# Callisto_Header_Test_Board.net
KiCad netlist of a schematic drawn in EAGLE
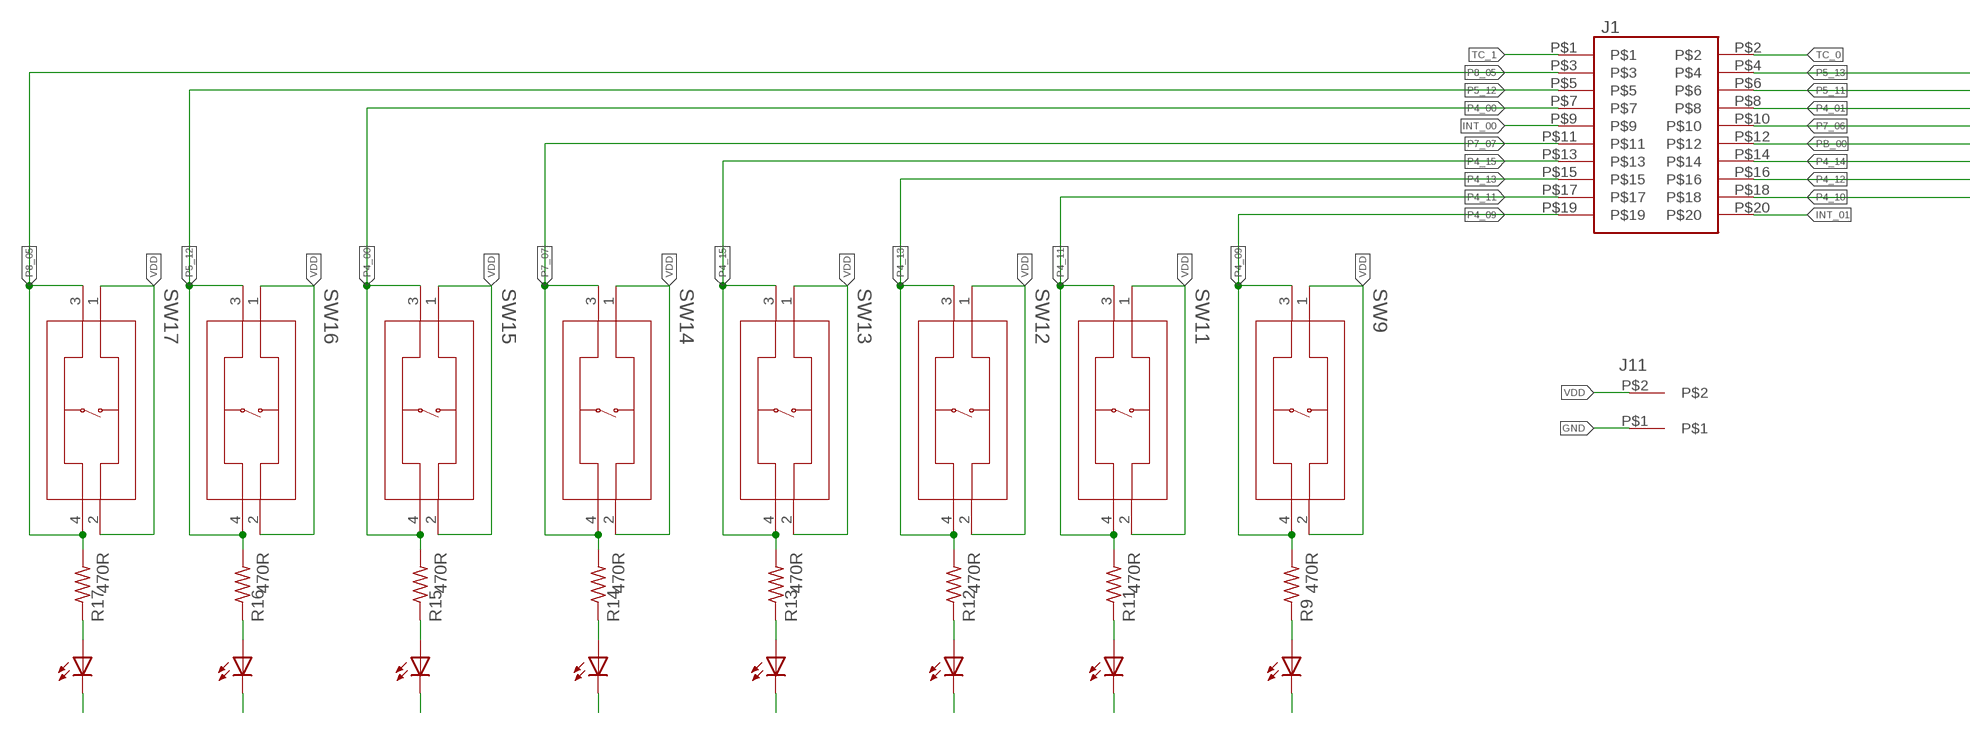
[diagram p0: schematic, sheet 1, part 1 of 2]
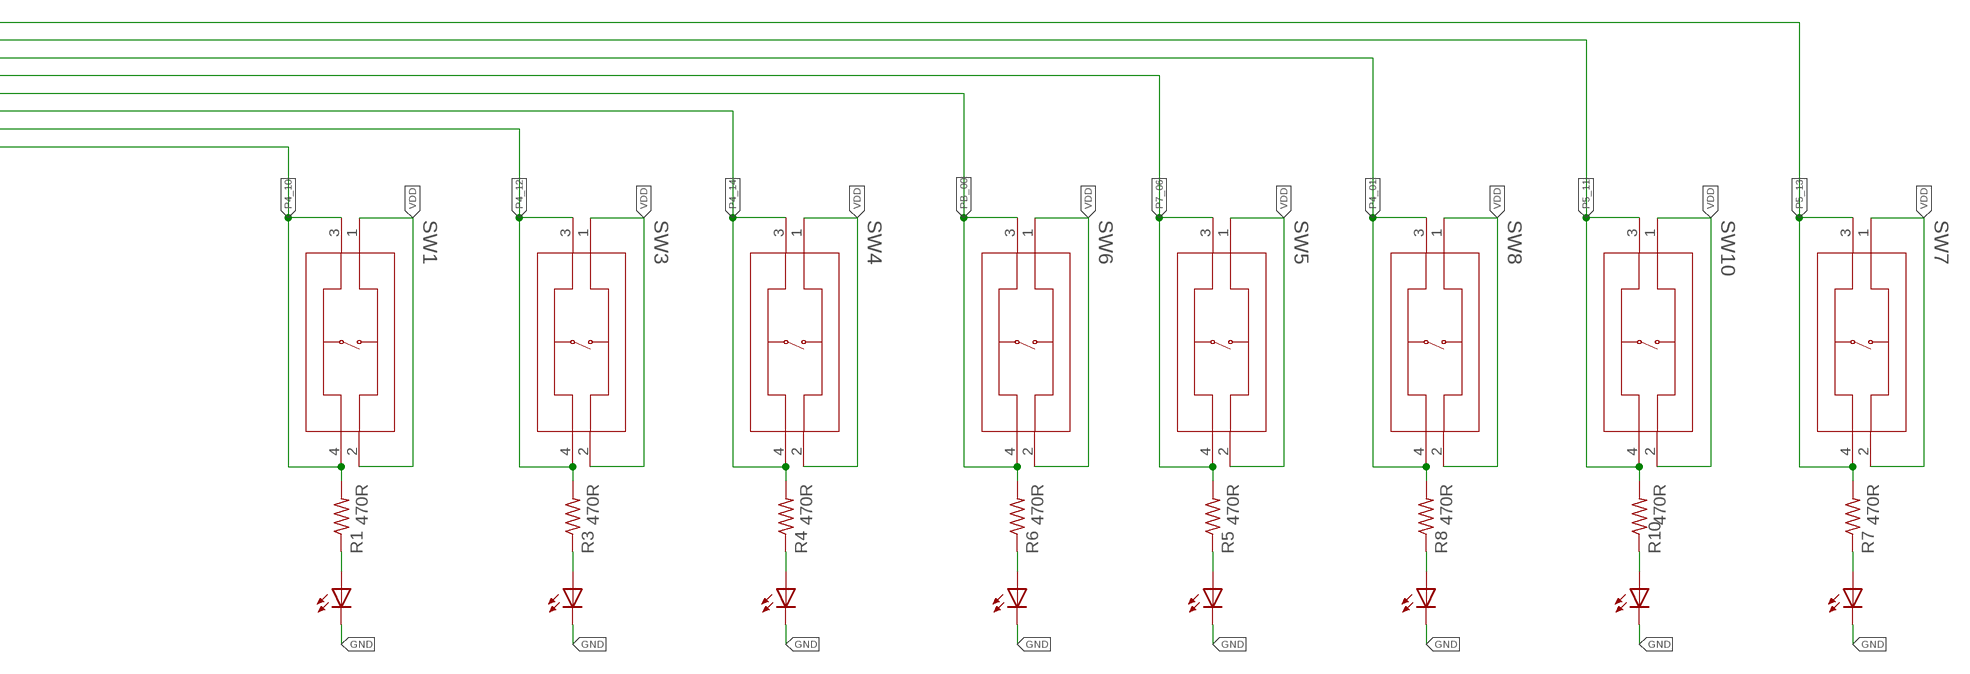
[diagram p1: schematic, sheet 1, part 2 of 2]

(export (version "E")
  (design (tool "Eeschema 10.0.6"))
  (components
    (comp (ref "J1")
      (value "20-pos")
      (footprint "eagle-import:2_X_10_.1_INCH")
      (fields (field (name "PARTNO") "67996-420HLF"))
      (libsource (lib "eagle-import") (part "2_X_10_HEADER_GENERIC"))
    )
    (comp (ref "J11")
      (value "2-pos")
      (footprint "eagle-import:2_3.81MM_PITCH")
      (fields (field (name "PARTNO") "691322310002"))
      (libsource (lib "eagle-import") (part "3.81MM_1_X_2_RT_ANGLE_PLUG_HEADER"))
    )
    (comp (ref "LED1")
      (value "Green")
      (footprint "eagle-import:0805")
      (fields (field (name "PARTNO") "LG R971-KN-1"))
      (libsource (lib "eagle-import") (part "LED_0805_GREEN"))
    )
    (comp (ref "LED3")
      (value "Green")
      (footprint "eagle-import:0805")
      (fields (field (name "PARTNO") "LG R971-KN-1"))
      (libsource (lib "eagle-import") (part "LED_0805_GREEN"))
    )
    (comp (ref "LED4")
      (value "Green")
      (footprint "eagle-import:0805")
      (fields (field (name "PARTNO") "LG R971-KN-1"))
      (libsource (lib "eagle-import") (part "LED_0805_GREEN"))
    )
    (comp (ref "LED5")
      (value "Green")
      (footprint "eagle-import:0805")
      (fields (field (name "PARTNO") "LG R971-KN-1"))
      (libsource (lib "eagle-import") (part "LED_0805_GREEN"))
    )
    (comp (ref "LED6")
      (value "Green")
      (footprint "eagle-import:0805")
      (fields (field (name "PARTNO") "LG R971-KN-1"))
      (libsource (lib "eagle-import") (part "LED_0805_GREEN"))
    )
    (comp (ref "LED7")
      (value "Green")
      (footprint "eagle-import:0805")
      (fields (field (name "PARTNO") "LG R971-KN-1"))
      (libsource (lib "eagle-import") (part "LED_0805_GREEN"))
    )
    (comp (ref "LED8")
      (value "Green")
      (footprint "eagle-import:0805")
      (fields (field (name "PARTNO") "LG R971-KN-1"))
      (libsource (lib "eagle-import") (part "LED_0805_GREEN"))
    )
    (comp (ref "LED9")
      (value "Green")
      (footprint "eagle-import:0805")
      (fields (field (name "PARTNO") "LG R971-KN-1"))
      (libsource (lib "eagle-import") (part "LED_0805_GREEN"))
    )
    (comp (ref "LED10")
      (value "Green")
      (footprint "eagle-import:0805")
      (fields (field (name "PARTNO") "LG R971-KN-1"))
      (libsource (lib "eagle-import") (part "LED_0805_GREEN"))
    )
    (comp (ref "LED11")
      (value "Green")
      (footprint "eagle-import:0805")
      (fields (field (name "PARTNO") "LG R971-KN-1"))
      (libsource (lib "eagle-import") (part "LED_0805_GREEN"))
    )
    (comp (ref "LED12")
      (value "Green")
      (footprint "eagle-import:0805")
      (fields (field (name "PARTNO") "LG R971-KN-1"))
      (libsource (lib "eagle-import") (part "LED_0805_GREEN"))
    )
    (comp (ref "LED13")
      (value "Green")
      (footprint "eagle-import:0805")
      (fields (field (name "PARTNO") "LG R971-KN-1"))
      (libsource (lib "eagle-import") (part "LED_0805_GREEN"))
    )
    (comp (ref "LED14")
      (value "Green")
      (footprint "eagle-import:0805")
      (fields (field (name "PARTNO") "LG R971-KN-1"))
      (libsource (lib "eagle-import") (part "LED_0805_GREEN"))
    )
    (comp (ref "LED15")
      (value "Green")
      (footprint "eagle-import:0805")
      (fields (field (name "PARTNO") "LG R971-KN-1"))
      (libsource (lib "eagle-import") (part "LED_0805_GREEN"))
    )
    (comp (ref "LED16")
      (value "Green")
      (footprint "eagle-import:0805")
      (fields (field (name "PARTNO") "LG R971-KN-1"))
      (libsource (lib "eagle-import") (part "LED_0805_GREEN"))
    )
    (comp (ref "LED17")
      (value "Green")
      (footprint "eagle-import:0805")
      (fields (field (name "PARTNO") "LG R971-KN-1"))
      (libsource (lib "eagle-import") (part "LED_0805_GREEN"))
    )
    (comp (ref "R1")
      (value "470R")
      (footprint "eagle-import:0402")
      (libsource (lib "eagle-import") (part "R_0402"))
    )
    (comp (ref "R3")
      (value "470R")
      (footprint "eagle-import:0402")
      (libsource (lib "eagle-import") (part "R_0402"))
    )
    (comp (ref "R4")
      (value "470R")
      (footprint "eagle-import:0402")
      (libsource (lib "eagle-import") (part "R_0402"))
    )
    (comp (ref "R5")
      (value "470R")
      (footprint "eagle-import:0402")
      (libsource (lib "eagle-import") (part "R_0402"))
    )
    (comp (ref "R6")
      (value "470R")
      (footprint "eagle-import:0402")
      (libsource (lib "eagle-import") (part "R_0402"))
    )
    (comp (ref "R7")
      (value "470R")
      (footprint "eagle-import:0402")
      (libsource (lib "eagle-import") (part "R_0402"))
    )
    (comp (ref "R8")
      (value "470R")
      (footprint "eagle-import:0402")
      (libsource (lib "eagle-import") (part "R_0402"))
    )
    (comp (ref "R9")
      (value "470R")
      (footprint "eagle-import:0402")
      (libsource (lib "eagle-import") (part "R_0402"))
    )
    (comp (ref "R10")
      (value "470R")
      (footprint "eagle-import:0402")
      (libsource (lib "eagle-import") (part "R_0402"))
    )
    (comp (ref "R11")
      (value "470R")
      (footprint "eagle-import:0402")
      (libsource (lib "eagle-import") (part "R_0402"))
    )
    (comp (ref "R12")
      (value "470R")
      (footprint "eagle-import:0402")
      (libsource (lib "eagle-import") (part "R_0402"))
    )
    (comp (ref "R13")
      (value "470R")
      (footprint "eagle-import:0402")
      (libsource (lib "eagle-import") (part "R_0402"))
    )
    (comp (ref "R14")
      (value "470R")
      (footprint "eagle-import:0402")
      (libsource (lib "eagle-import") (part "R_0402"))
    )
    (comp (ref "R15")
      (value "470R")
      (footprint "eagle-import:0402")
      (libsource (lib "eagle-import") (part "R_0402"))
    )
    (comp (ref "R16")
      (value "470R")
      (footprint "eagle-import:0402")
      (libsource (lib "eagle-import") (part "R_0402"))
    )
    (comp (ref "R17")
      (value "470R")
      (footprint "eagle-import:0402")
      (libsource (lib "eagle-import") (part "R_0402"))
    )
    (comp (ref "SW1")
      (value "PTS810SJG250SMTRLFS")
      (footprint "eagle-import:PTS810")
      (fields (field (name "COPYRIGHT") "Copyright (C) 2018 Accelerated Designs. All rights reserved"))
      (libsource (lib "eagle-import") (part "PTS810SJG250SMTRLFS"))
    )
    (comp (ref "SW3")
      (value "PTS810SJG250SMTRLFS")
      (footprint "eagle-import:PTS810")
      (fields (field (name "COPYRIGHT") "Copyright (C) 2018 Accelerated Designs. All rights reserved"))
      (libsource (lib "eagle-import") (part "PTS810SJG250SMTRLFS"))
    )
    (comp (ref "SW4")
      (value "PTS810SJG250SMTRLFS")
      (footprint "eagle-import:PTS810")
      (fields (field (name "COPYRIGHT") "Copyright (C) 2018 Accelerated Designs. All rights reserved"))
      (libsource (lib "eagle-import") (part "PTS810SJG250SMTRLFS"))
    )
    (comp (ref "SW5")
      (value "PTS810SJG250SMTRLFS")
      (footprint "eagle-import:PTS810")
      (fields (field (name "COPYRIGHT") "Copyright (C) 2018 Accelerated Designs. All rights reserved"))
      (libsource (lib "eagle-import") (part "PTS810SJG250SMTRLFS"))
    )
    (comp (ref "SW6")
      (value "PTS810SJG250SMTRLFS")
      (footprint "eagle-import:PTS810")
      (fields (field (name "COPYRIGHT") "Copyright (C) 2018 Accelerated Designs. All rights reserved"))
      (libsource (lib "eagle-import") (part "PTS810SJG250SMTRLFS"))
    )
    (comp (ref "SW7")
      (value "PTS810SJG250SMTRLFS")
      (footprint "eagle-import:PTS810")
      (fields (field (name "COPYRIGHT") "Copyright (C) 2018 Accelerated Designs. All rights reserved"))
      (libsource (lib "eagle-import") (part "PTS810SJG250SMTRLFS"))
    )
    (comp (ref "SW8")
      (value "PTS810SJG250SMTRLFS")
      (footprint "eagle-import:PTS810")
      (fields (field (name "COPYRIGHT") "Copyright (C) 2018 Accelerated Designs. All rights reserved"))
      (libsource (lib "eagle-import") (part "PTS810SJG250SMTRLFS"))
    )
    (comp (ref "SW9")
      (value "PTS810SJG250SMTRLFS")
      (footprint "eagle-import:PTS810")
      (fields (field (name "COPYRIGHT") "Copyright (C) 2018 Accelerated Designs. All rights reserved"))
      (libsource (lib "eagle-import") (part "PTS810SJG250SMTRLFS"))
    )
    (comp (ref "SW10")
      (value "PTS810SJG250SMTRLFS")
      (footprint "eagle-import:PTS810")
      (fields (field (name "COPYRIGHT") "Copyright (C) 2018 Accelerated Designs. All rights reserved"))
      (libsource (lib "eagle-import") (part "PTS810SJG250SMTRLFS"))
    )
    (comp (ref "SW11")
      (value "PTS810SJG250SMTRLFS")
      (footprint "eagle-import:PTS810")
      (fields (field (name "COPYRIGHT") "Copyright (C) 2018 Accelerated Designs. All rights reserved"))
      (libsource (lib "eagle-import") (part "PTS810SJG250SMTRLFS"))
    )
    (comp (ref "SW12")
      (value "PTS810SJG250SMTRLFS")
      (footprint "eagle-import:PTS810")
      (fields (field (name "COPYRIGHT") "Copyright (C) 2018 Accelerated Designs. All rights reserved"))
      (libsource (lib "eagle-import") (part "PTS810SJG250SMTRLFS"))
    )
    (comp (ref "SW13")
      (value "PTS810SJG250SMTRLFS")
      (footprint "eagle-import:PTS810")
      (fields (field (name "COPYRIGHT") "Copyright (C) 2018 Accelerated Designs. All rights reserved"))
      (libsource (lib "eagle-import") (part "PTS810SJG250SMTRLFS"))
    )
    (comp (ref "SW14")
      (value "PTS810SJG250SMTRLFS")
      (footprint "eagle-import:PTS810")
      (fields (field (name "COPYRIGHT") "Copyright (C) 2018 Accelerated Designs. All rights reserved"))
      (libsource (lib "eagle-import") (part "PTS810SJG250SMTRLFS"))
    )
    (comp (ref "SW15")
      (value "PTS810SJG250SMTRLFS")
      (footprint "eagle-import:PTS810")
      (fields (field (name "COPYRIGHT") "Copyright (C) 2018 Accelerated Designs. All rights reserved"))
      (libsource (lib "eagle-import") (part "PTS810SJG250SMTRLFS"))
    )
    (comp (ref "SW16")
      (value "PTS810SJG250SMTRLFS")
      (footprint "eagle-import:PTS810")
      (fields (field (name "COPYRIGHT") "Copyright (C) 2018 Accelerated Designs. All rights reserved"))
      (libsource (lib "eagle-import") (part "PTS810SJG250SMTRLFS"))
    )
    (comp (ref "SW17")
      (value "PTS810SJG250SMTRLFS")
      (footprint "eagle-import:PTS810")
      (fields (field (name "COPYRIGHT") "Copyright (C) 2018 Accelerated Designs. All rights reserved"))
      (libsource (lib "eagle-import") (part "PTS810SJG250SMTRLFS"))
    )
  )
  (nets
    (net (code "1") (name "GND") (class "Default")
      (node (ref "J11") (pin "P$1") (pinfunction "P$1_P$1") (pintype "bidirectional"))
      (node (ref "LED1") (pin "2") (pinfunction "C_2") (pintype "passive"))
      (node (ref "LED10") (pin "2") (pinfunction "C_2") (pintype "passive"))
      (node (ref "LED11") (pin "2") (pinfunction "C_2") (pintype "passive"))
      (node (ref "LED12") (pin "2") (pinfunction "C_2") (pintype "passive"))
      (node (ref "LED13") (pin "2") (pinfunction "C_2") (pintype "passive"))
      (node (ref "LED14") (pin "2") (pinfunction "C_2") (pintype "passive"))
      (node (ref "LED15") (pin "2") (pinfunction "C_2") (pintype "passive"))
      (node (ref "LED16") (pin "2") (pinfunction "C_2") (pintype "passive"))
      (node (ref "LED17") (pin "2") (pinfunction "C_2") (pintype "passive"))
      (node (ref "LED3") (pin "2") (pinfunction "C_2") (pintype "passive"))
      (node (ref "LED4") (pin "2") (pinfunction "C_2") (pintype "passive"))
      (node (ref "LED5") (pin "2") (pinfunction "C_2") (pintype "passive"))
      (node (ref "LED6") (pin "2") (pinfunction "C_2") (pintype "passive"))
      (node (ref "LED7") (pin "2") (pinfunction "C_2") (pintype "passive"))
      (node (ref "LED8") (pin "2") (pinfunction "C_2") (pintype "passive"))
      (node (ref "LED9") (pin "2") (pinfunction "C_2") (pintype "passive"))
    )
    (net (code "2") (name "INT_00") (class "Default")
      (node (ref "J1") (pin "P$9") (pinfunction "P$9_P$9") (pintype "bidirectional"))
    )
    (net (code "3") (name "INT_01") (class "Default")
      (node (ref "J1") (pin "P$20") (pinfunction "P$20_P$20") (pintype "bidirectional"))
    )
    (net (code "4") (name "Net-(LED1-A)") (class "Default")
      (node (ref "LED1") (pin "1") (pinfunction "A_1") (pintype "passive"))
      (node (ref "R1") (pin "P$1") (pinfunction "1_P$1") (pintype "passive"))
    )
    (net (code "5") (name "Net-(LED3-A)") (class "Default")
      (node (ref "LED3") (pin "1") (pinfunction "A_1") (pintype "passive"))
      (node (ref "R3") (pin "P$1") (pinfunction "1_P$1") (pintype "passive"))
    )
    (net (code "6") (name "Net-(LED4-A)") (class "Default")
      (node (ref "LED4") (pin "1") (pinfunction "A_1") (pintype "passive"))
      (node (ref "R4") (pin "P$1") (pinfunction "1_P$1") (pintype "passive"))
    )
    (net (code "7") (name "Net-(LED5-A)") (class "Default")
      (node (ref "LED5") (pin "1") (pinfunction "A_1") (pintype "passive"))
      (node (ref "R5") (pin "P$1") (pinfunction "1_P$1") (pintype "passive"))
    )
    (net (code "8") (name "Net-(LED6-A)") (class "Default")
      (node (ref "LED6") (pin "1") (pinfunction "A_1") (pintype "passive"))
      (node (ref "R6") (pin "P$1") (pinfunction "1_P$1") (pintype "passive"))
    )
    (net (code "9") (name "Net-(LED7-A)") (class "Default")
      (node (ref "LED7") (pin "1") (pinfunction "A_1") (pintype "passive"))
      (node (ref "R7") (pin "P$1") (pinfunction "1_P$1") (pintype "passive"))
    )
    (net (code "10") (name "Net-(LED8-A)") (class "Default")
      (node (ref "LED8") (pin "1") (pinfunction "A_1") (pintype "passive"))
      (node (ref "R8") (pin "P$1") (pinfunction "1_P$1") (pintype "passive"))
    )
    (net (code "11") (name "Net-(LED9-A)") (class "Default")
      (node (ref "LED9") (pin "1") (pinfunction "A_1") (pintype "passive"))
      (node (ref "R9") (pin "P$1") (pinfunction "1_P$1") (pintype "passive"))
    )
    (net (code "12") (name "Net-(LED10-A)") (class "Default")
      (node (ref "LED10") (pin "1") (pinfunction "A_1") (pintype "passive"))
      (node (ref "R10") (pin "P$1") (pinfunction "1_P$1") (pintype "passive"))
    )
    (net (code "13") (name "Net-(LED11-A)") (class "Default")
      (node (ref "LED11") (pin "1") (pinfunction "A_1") (pintype "passive"))
      (node (ref "R11") (pin "P$1") (pinfunction "1_P$1") (pintype "passive"))
    )
    (net (code "14") (name "Net-(LED12-A)") (class "Default")
      (node (ref "LED12") (pin "1") (pinfunction "A_1") (pintype "passive"))
      (node (ref "R12") (pin "P$1") (pinfunction "1_P$1") (pintype "passive"))
    )
    (net (code "15") (name "Net-(LED13-A)") (class "Default")
      (node (ref "LED13") (pin "1") (pinfunction "A_1") (pintype "passive"))
      (node (ref "R13") (pin "P$1") (pinfunction "1_P$1") (pintype "passive"))
    )
    (net (code "16") (name "Net-(LED14-A)") (class "Default")
      (node (ref "LED14") (pin "1") (pinfunction "A_1") (pintype "passive"))
      (node (ref "R14") (pin "P$1") (pinfunction "1_P$1") (pintype "passive"))
    )
    (net (code "17") (name "Net-(LED15-A)") (class "Default")
      (node (ref "LED15") (pin "1") (pinfunction "A_1") (pintype "passive"))
      (node (ref "R15") (pin "P$1") (pinfunction "1_P$1") (pintype "passive"))
    )
    (net (code "18") (name "Net-(LED16-A)") (class "Default")
      (node (ref "LED16") (pin "1") (pinfunction "A_1") (pintype "passive"))
      (node (ref "R16") (pin "P$1") (pinfunction "1_P$1") (pintype "passive"))
    )
    (net (code "19") (name "Net-(LED17-A)") (class "Default")
      (node (ref "LED17") (pin "1") (pinfunction "A_1") (pintype "passive"))
      (node (ref "R17") (pin "P$1") (pinfunction "1_P$1") (pintype "passive"))
    )
    (net (code "20") (name "P4_00") (class "Default")
      (node (ref "J1") (pin "P$7") (pinfunction "P$7_P$7") (pintype "bidirectional"))
      (node (ref "R15") (pin "P$2") (pinfunction "2_P$2") (pintype "passive"))
      (node (ref "SW15") (pin "3") (pinfunction "3_3") (pintype "passive"))
      (node (ref "SW15") (pin "4") (pinfunction "4_4") (pintype "passive"))
    )
    (net (code "21") (name "P4_01") (class "Default")
      (node (ref "J1") (pin "P$8") (pinfunction "P$8_P$8") (pintype "bidirectional"))
      (node (ref "R8") (pin "P$2") (pinfunction "2_P$2") (pintype "passive"))
      (node (ref "SW8") (pin "3") (pinfunction "3_3") (pintype "passive"))
      (node (ref "SW8") (pin "4") (pinfunction "4_4") (pintype "passive"))
    )
    (net (code "22") (name "P4_09") (class "Default")
      (node (ref "J1") (pin "P$19") (pinfunction "P$19_P$19") (pintype "bidirectional"))
      (node (ref "R9") (pin "P$2") (pinfunction "2_P$2") (pintype "passive"))
      (node (ref "SW9") (pin "3") (pinfunction "3_3") (pintype "passive"))
      (node (ref "SW9") (pin "4") (pinfunction "4_4") (pintype "passive"))
    )
    (net (code "23") (name "P4_10") (class "Default")
      (node (ref "J1") (pin "P$18") (pinfunction "P$18_P$18") (pintype "bidirectional"))
      (node (ref "R1") (pin "P$2") (pinfunction "2_P$2") (pintype "passive"))
      (node (ref "SW1") (pin "3") (pinfunction "3_3") (pintype "passive"))
      (node (ref "SW1") (pin "4") (pinfunction "4_4") (pintype "passive"))
    )
    (net (code "24") (name "P4_11") (class "Default")
      (node (ref "J1") (pin "P$17") (pinfunction "P$17_P$17") (pintype "bidirectional"))
      (node (ref "R11") (pin "P$2") (pinfunction "2_P$2") (pintype "passive"))
      (node (ref "SW11") (pin "3") (pinfunction "3_3") (pintype "passive"))
      (node (ref "SW11") (pin "4") (pinfunction "4_4") (pintype "passive"))
    )
    (net (code "25") (name "P4_12") (class "Default")
      (node (ref "J1") (pin "P$16") (pinfunction "P$16_P$16") (pintype "bidirectional"))
      (node (ref "R3") (pin "P$2") (pinfunction "2_P$2") (pintype "passive"))
      (node (ref "SW3") (pin "3") (pinfunction "3_3") (pintype "passive"))
      (node (ref "SW3") (pin "4") (pinfunction "4_4") (pintype "passive"))
    )
    (net (code "26") (name "P4_13") (class "Default")
      (node (ref "J1") (pin "P$15") (pinfunction "P$15_P$15") (pintype "bidirectional"))
      (node (ref "R12") (pin "P$2") (pinfunction "2_P$2") (pintype "passive"))
      (node (ref "SW12") (pin "3") (pinfunction "3_3") (pintype "passive"))
      (node (ref "SW12") (pin "4") (pinfunction "4_4") (pintype "passive"))
    )
    (net (code "27") (name "P4_14") (class "Default")
      (node (ref "J1") (pin "P$14") (pinfunction "P$14_P$14") (pintype "bidirectional"))
      (node (ref "R4") (pin "P$2") (pinfunction "2_P$2") (pintype "passive"))
      (node (ref "SW4") (pin "3") (pinfunction "3_3") (pintype "passive"))
      (node (ref "SW4") (pin "4") (pinfunction "4_4") (pintype "passive"))
    )
    (net (code "28") (name "P4_15") (class "Default")
      (node (ref "J1") (pin "P$13") (pinfunction "P$13_P$13") (pintype "bidirectional"))
      (node (ref "R13") (pin "P$2") (pinfunction "2_P$2") (pintype "passive"))
      (node (ref "SW13") (pin "3") (pinfunction "3_3") (pintype "passive"))
      (node (ref "SW13") (pin "4") (pinfunction "4_4") (pintype "passive"))
    )
    (net (code "29") (name "P5_11") (class "Default")
      (node (ref "J1") (pin "P$6") (pinfunction "P$6_P$6") (pintype "bidirectional"))
      (node (ref "R10") (pin "P$2") (pinfunction "2_P$2") (pintype "passive"))
      (node (ref "SW10") (pin "3") (pinfunction "3_3") (pintype "passive"))
      (node (ref "SW10") (pin "4") (pinfunction "4_4") (pintype "passive"))
    )
    (net (code "30") (name "P5_12") (class "Default")
      (node (ref "J1") (pin "P$5") (pinfunction "P$5_P$5") (pintype "bidirectional"))
      (node (ref "R16") (pin "P$2") (pinfunction "2_P$2") (pintype "passive"))
      (node (ref "SW16") (pin "3") (pinfunction "3_3") (pintype "passive"))
      (node (ref "SW16") (pin "4") (pinfunction "4_4") (pintype "passive"))
    )
    (net (code "31") (name "P5_13") (class "Default")
      (node (ref "J1") (pin "P$4") (pinfunction "P$4_P$4") (pintype "bidirectional"))
      (node (ref "R7") (pin "P$2") (pinfunction "2_P$2") (pintype "passive"))
      (node (ref "SW7") (pin "3") (pinfunction "3_3") (pintype "passive"))
      (node (ref "SW7") (pin "4") (pinfunction "4_4") (pintype "passive"))
    )
    (net (code "32") (name "P7_06") (class "Default")
      (node (ref "J1") (pin "P$10") (pinfunction "P$10_P$10") (pintype "bidirectional"))
      (node (ref "R5") (pin "P$2") (pinfunction "2_P$2") (pintype "passive"))
      (node (ref "SW5") (pin "3") (pinfunction "3_3") (pintype "passive"))
      (node (ref "SW5") (pin "4") (pinfunction "4_4") (pintype "passive"))
    )
    (net (code "33") (name "P7_07") (class "Default")
      (node (ref "J1") (pin "P$11") (pinfunction "P$11_P$11") (pintype "bidirectional"))
      (node (ref "R14") (pin "P$2") (pinfunction "2_P$2") (pintype "passive"))
      (node (ref "SW14") (pin "3") (pinfunction "3_3") (pintype "passive"))
      (node (ref "SW14") (pin "4") (pinfunction "4_4") (pintype "passive"))
    )
    (net (code "34") (name "P8_05") (class "Default")
      (node (ref "J1") (pin "P$3") (pinfunction "P$3_P$3") (pintype "bidirectional"))
      (node (ref "R17") (pin "P$2") (pinfunction "2_P$2") (pintype "passive"))
      (node (ref "SW17") (pin "3") (pinfunction "3_3") (pintype "passive"))
      (node (ref "SW17") (pin "4") (pinfunction "4_4") (pintype "passive"))
    )
    (net (code "35") (name "PB_00") (class "Default")
      (node (ref "J1") (pin "P$12") (pinfunction "P$12_P$12") (pintype "bidirectional"))
      (node (ref "R6") (pin "P$2") (pinfunction "2_P$2") (pintype "passive"))
      (node (ref "SW6") (pin "3") (pinfunction "3_3") (pintype "passive"))
      (node (ref "SW6") (pin "4") (pinfunction "4_4") (pintype "passive"))
    )
    (net (code "36") (name "TC_0") (class "Default")
      (node (ref "J1") (pin "P$2") (pinfunction "P$2_P$2") (pintype "bidirectional"))
    )
    (net (code "37") (name "TC_1") (class "Default")
      (node (ref "J1") (pin "P$1") (pinfunction "P$1_P$1") (pintype "bidirectional"))
    )
    (net (code "38") (name "VDD") (class "Default")
      (node (ref "J11") (pin "P$2") (pinfunction "P$2_P$2") (pintype "bidirectional"))
      (node (ref "SW1") (pin "1") (pinfunction "1_1") (pintype "passive"))
      (node (ref "SW1") (pin "2") (pinfunction "2_2") (pintype "passive"))
      (node (ref "SW10") (pin "1") (pinfunction "1_1") (pintype "passive"))
      (node (ref "SW10") (pin "2") (pinfunction "2_2") (pintype "passive"))
      (node (ref "SW11") (pin "1") (pinfunction "1_1") (pintype "passive"))
      (node (ref "SW11") (pin "2") (pinfunction "2_2") (pintype "passive"))
      (node (ref "SW12") (pin "1") (pinfunction "1_1") (pintype "passive"))
      (node (ref "SW12") (pin "2") (pinfunction "2_2") (pintype "passive"))
      (node (ref "SW13") (pin "1") (pinfunction "1_1") (pintype "passive"))
      (node (ref "SW13") (pin "2") (pinfunction "2_2") (pintype "passive"))
      (node (ref "SW14") (pin "1") (pinfunction "1_1") (pintype "passive"))
      (node (ref "SW14") (pin "2") (pinfunction "2_2") (pintype "passive"))
      (node (ref "SW15") (pin "1") (pinfunction "1_1") (pintype "passive"))
      (node (ref "SW15") (pin "2") (pinfunction "2_2") (pintype "passive"))
      (node (ref "SW16") (pin "1") (pinfunction "1_1") (pintype "passive"))
      (node (ref "SW16") (pin "2") (pinfunction "2_2") (pintype "passive"))
      (node (ref "SW17") (pin "1") (pinfunction "1_1") (pintype "passive"))
      (node (ref "SW17") (pin "2") (pinfunction "2_2") (pintype "passive"))
      (node (ref "SW3") (pin "1") (pinfunction "1_1") (pintype "passive"))
      (node (ref "SW3") (pin "2") (pinfunction "2_2") (pintype "passive"))
      (node (ref "SW4") (pin "1") (pinfunction "1_1") (pintype "passive"))
      (node (ref "SW4") (pin "2") (pinfunction "2_2") (pintype "passive"))
      (node (ref "SW5") (pin "1") (pinfunction "1_1") (pintype "passive"))
      (node (ref "SW5") (pin "2") (pinfunction "2_2") (pintype "passive"))
      (node (ref "SW6") (pin "1") (pinfunction "1_1") (pintype "passive"))
      (node (ref "SW6") (pin "2") (pinfunction "2_2") (pintype "passive"))
      (node (ref "SW7") (pin "1") (pinfunction "1_1") (pintype "passive"))
      (node (ref "SW7") (pin "2") (pinfunction "2_2") (pintype "passive"))
      (node (ref "SW8") (pin "1") (pinfunction "1_1") (pintype "passive"))
      (node (ref "SW8") (pin "2") (pinfunction "2_2") (pintype "passive"))
      (node (ref "SW9") (pin "1") (pinfunction "1_1") (pintype "passive"))
      (node (ref "SW9") (pin "2") (pinfunction "2_2") (pintype "passive"))
    )
  )
)
